# DoXeArduino_RFID.net
KiCad netlist of a schematic drawn in Altium Designer
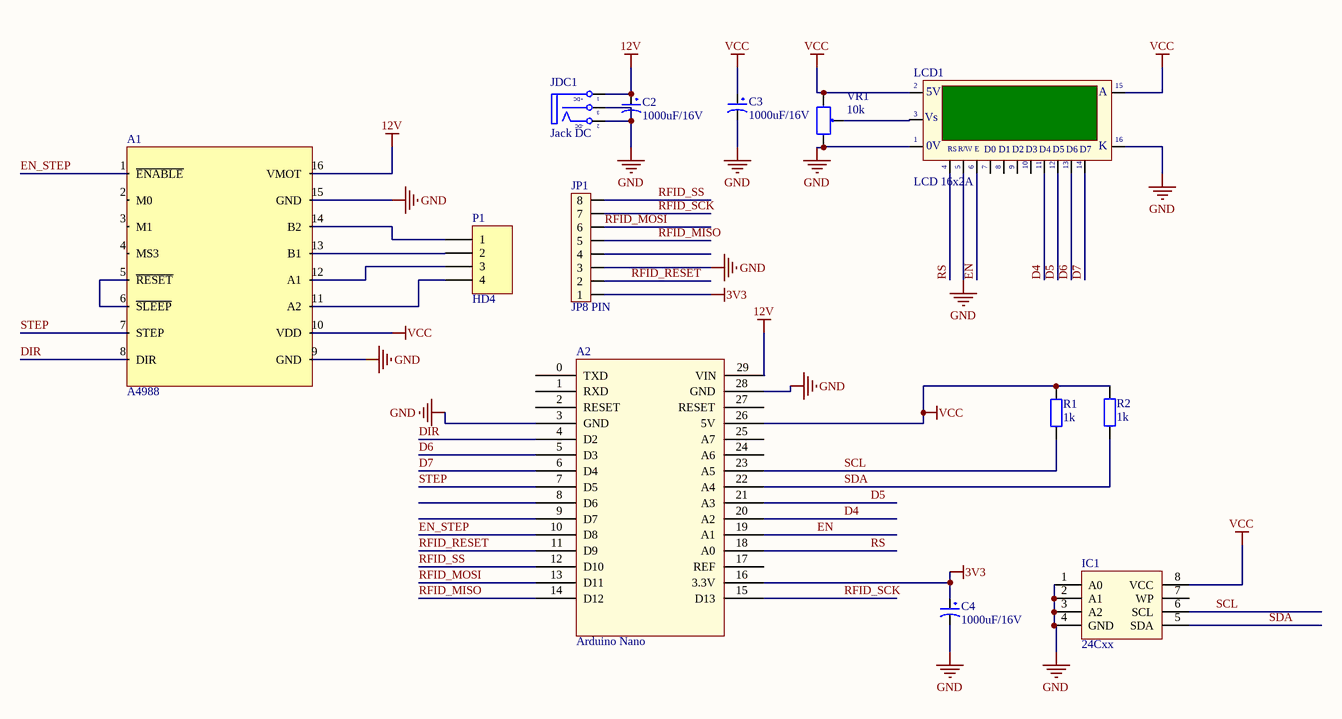
[diagram p0: DoXeArduino_RFID.SchDoc]

(export (version "E")
  (design (tool "Eeschema 10.0.6"))
  (components
    (comp (ref "A1") (value "A4988") (footprint "A4988") (libsource (lib "OBIT_TESLA") (part "A4988")))
    (comp (ref "A2")
      (value "Arduino Nano")
      (footprint "Arduino Nano")
      (libsource (lib "OBIT_TESLA") (part "Arduino Nano"))
    )
    (comp (ref "C2")
      (value "1000uF/16V")
      (footprint "CP1.5/3.4")
      (description "Cap 1000uF/16V - 220uF/50V")
      (libsource (lib "OBIT_TESLA") (part "CP4"))
    )
    (comp (ref "C3")
      (value "1000uF/16V")
      (footprint "CP1.5/3.4")
      (description "Cap 1000uF/16V - 220uF/50V")
      (libsource (lib "OBIT_TESLA") (part "CP4"))
    )
    (comp (ref "C4")
      (value "1000uF/16V")
      (footprint "CP1.5/3.4")
      (description "Cap 1000uF/16V - 220uF/50V")
      (libsource (lib "OBIT_TESLA") (part "CP4"))
    )
    (comp (ref "IC1")
      (value "24Cxx")
      (footprint "DIP8/W0.3")
      (description "Standard 2-Wire Bus Interface Serial EEPROM")
      (fields (field (name "COPYRIGHT BY") "VanDungEvn"))
      (libsource (lib "Obit_Library") (part "24Cxx"))
    )
    (comp (ref "JDC1") (value "Jack DC") (footprint "DC0") (libsource (lib "OBIT_TESLA") (part "JACK_DC")))
    (comp (ref "JP1") (value "JP8 PIN") (footprint "JP8") (libsource (lib "Obit_Library") (part "JP8")))
    (comp (ref "LCD1")
      (value "LCD 16x2A")
      (footprint "LCD16X2")
      (description "LCD dipslay 16 char, 2 line")
      (libsource (lib "OBIT_TESLA") (part "LCD16x2A"))
    )
    (comp (ref "P1") (value "HD4") (footprint "HEADER 4") (libsource (lib "OBIT_TESLA") (part "HEADER 4")))
    (comp (ref "R1")
      (value "1k")
      (footprint "RES-SMD-0805")
      (description "Resistor R1/4W")
      (libsource (lib "OBIT_TESLA") (part "R"))
    )
    (comp (ref "R2")
      (value "1k")
      (footprint "RES-SMD-0805")
      (description "Resistor R1/4W")
      (libsource (lib "OBIT_TESLA") (part "R"))
    )
    (comp (ref "VR1") (value "10k") (footprint "VR-S2") (libsource (lib "OBIT_TESLA") (part "Resistor Var")))
  )
  (nets
    (net (code "1") (name "/D4") (class "Default")
      (node (ref "A2") (pin "20") (pinfunction "A2_20") (pintype "passive"))
      (node (ref "LCD1") (pin "11") (pinfunction "D4_11") (pintype "passive"))
    )
    (net (code "2") (name "/D5") (class "Default")
      (node (ref "A2") (pin "21") (pinfunction "A3_21") (pintype "passive"))
      (node (ref "LCD1") (pin "12") (pinfunction "D5_12") (pintype "passive"))
    )
    (net (code "3") (name "/D6") (class "Default")
      (node (ref "A2") (pin "5") (pinfunction "D3_5") (pintype "passive"))
      (node (ref "LCD1") (pin "13") (pinfunction "D6_13") (pintype "passive"))
    )
    (net (code "4") (name "/D7") (class "Default")
      (node (ref "A2") (pin "6") (pinfunction "D4_6") (pintype "passive"))
      (node (ref "LCD1") (pin "14") (pinfunction "D7_14") (pintype "passive"))
    )
    (net (code "5") (name "/DIR") (class "Default")
      (node (ref "A1") (pin "8") (pinfunction "DIR_8") (pintype "passive"))
      (node (ref "A2") (pin "4") (pinfunction "D2_4") (pintype "passive"))
    )
    (net (code "6") (name "/EN") (class "Default")
      (node (ref "A2") (pin "19") (pinfunction "A1_19") (pintype "passive"))
      (node (ref "LCD1") (pin "6") (pinfunction "~{EN}_6") (pintype "passive"))
    )
    (net (code "7") (name "/EN_STEP") (class "Default")
      (node (ref "A1") (pin "1") (pinfunction "~{ENABLE}_1") (pintype "passive"))
      (node (ref "A2") (pin "10") (pinfunction "D8_10") (pintype "passive"))
    )
    (net (code "8") (name "/RFID_MISO") (class "Default")
      (node (ref "A2") (pin "14") (pinfunction "D12_14") (pintype "passive"))
      (node (ref "JP1") (pin "5") (pinfunction "5_5") (pintype "passive"))
    )
    (net (code "9") (name "/RFID_MOSI") (class "Default")
      (node (ref "A2") (pin "13") (pinfunction "D11_13") (pintype "passive"))
      (node (ref "JP1") (pin "6") (pinfunction "6_6") (pintype "passive"))
    )
    (net (code "10") (name "/RFID_RESET") (class "Default")
      (node (ref "A2") (pin "11") (pinfunction "D9_11") (pintype "passive"))
      (node (ref "JP1") (pin "2") (pinfunction "2_2") (pintype "passive"))
    )
    (net (code "11") (name "/RFID_SCK") (class "Default")
      (node (ref "A2") (pin "15") (pinfunction "D13_15") (pintype "passive"))
      (node (ref "JP1") (pin "7") (pinfunction "7_7") (pintype "passive"))
    )
    (net (code "12") (name "/RFID_SS") (class "Default")
      (node (ref "A2") (pin "12") (pinfunction "D10_12") (pintype "passive"))
      (node (ref "JP1") (pin "8") (pinfunction "8_8") (pintype "passive"))
    )
    (net (code "13") (name "/RS") (class "Default")
      (node (ref "A2") (pin "18") (pinfunction "A0_18") (pintype "passive"))
      (node (ref "LCD1") (pin "4") (pinfunction "RS_4") (pintype "passive"))
    )
    (net (code "14") (name "/SCL") (class "Default")
      (node (ref "A2") (pin "23") (pinfunction "A5_23") (pintype "passive"))
      (node (ref "IC1") (pin "6") (pinfunction "SCL_6") (pintype "passive"))
      (node (ref "R1") (pin "1") (pinfunction "1_1") (pintype "passive"))
    )
    (net (code "15") (name "/SDA") (class "Default")
      (node (ref "A2") (pin "22") (pinfunction "A4_22") (pintype "passive"))
      (node (ref "IC1") (pin "5") (pinfunction "SDA_5") (pintype "passive"))
      (node (ref "R2") (pin "1") (pinfunction "1_1") (pintype "passive"))
    )
    (net (code "16") (name "/STEP") (class "Default")
      (node (ref "A1") (pin "7") (pinfunction "STEP_7") (pintype "passive"))
      (node (ref "A2") (pin "7") (pinfunction "D5_7") (pintype "passive"))
    )
    (net (code "17") (name "3V3") (class "Default")
      (node (ref "A2") (pin "16") (pinfunction "3.3V_16") (pintype "passive"))
      (node (ref "C4") (pin "1") (pinfunction "1_1") (pintype "passive"))
      (node (ref "JP1") (pin "1") (pinfunction "1_1") (pintype "passive"))
    )
    (net (code "18") (name "12V") (class "Default")
      (node (ref "A1") (pin "16") (pinfunction "VMOT_16") (pintype "passive"))
      (node (ref "A2") (pin "29") (pinfunction "VIN_29") (pintype "passive"))
      (node (ref "C2") (pin "1") (pinfunction "1_1") (pintype "passive"))
      (node (ref "JDC1") (pin "1") (pinfunction "T_1") (pintype "passive"))
    )
    (net (code "19") (name "GND") (class "Default")
      (node (ref "A1") (pin "15") (pinfunction "GND_15") (pintype "passive"))
      (node (ref "A1") (pin "9") (pinfunction "GND_9") (pintype "passive"))
      (node (ref "A2") (pin "28") (pinfunction "GND_28") (pintype "passive"))
      (node (ref "A2") (pin "3") (pinfunction "GND_3") (pintype "passive"))
      (node (ref "C2") (pin "2") (pinfunction "2_2") (pintype "passive"))
      (node (ref "C3") (pin "2") (pinfunction "2_2") (pintype "passive"))
      (node (ref "C4") (pin "2") (pinfunction "2_2") (pintype "passive"))
      (node (ref "IC1") (pin "1") (pinfunction "A0_1") (pintype "passive"))
      (node (ref "IC1") (pin "2") (pinfunction "A1_2") (pintype "passive"))
      (node (ref "IC1") (pin "3") (pinfunction "A2_3") (pintype "passive"))
      (node (ref "IC1") (pin "4") (pinfunction "GND_4") (pintype "power_in"))
      (node (ref "JDC1") (pin "2") (pinfunction "TN_2") (pintype "passive"))
      (node (ref "JDC1") (pin "3") (pinfunction "S_3") (pintype "power_in"))
      (node (ref "JP1") (pin "3") (pinfunction "3_3") (pintype "passive"))
      (node (ref "LCD1") (pin "1") (pinfunction "GND_1") (pintype "passive"))
      (node (ref "LCD1") (pin "16") (pinfunction "K_16") (pintype "passive"))
      (node (ref "LCD1") (pin "5") (pinfunction "R/~{W}_5") (pintype "passive"))
      (node (ref "VR1") (pin "3") (pinfunction "3_3") (pintype "passive"))
    )
    (net (code "20") (name "Net-(A1-A1)") (class "Default")
      (node (ref "A1") (pin "12") (pinfunction "A1_12") (pintype "passive"))
      (node (ref "P1") (pin "3") (pinfunction "3_3") (pintype "passive"))
    )
    (net (code "21") (name "Net-(A1-A2)") (class "Default")
      (node (ref "A1") (pin "11") (pinfunction "A2_11") (pintype "passive"))
      (node (ref "P1") (pin "4") (pinfunction "4_4") (pintype "passive"))
    )
    (net (code "22") (name "Net-(A1-B1)") (class "Default")
      (node (ref "A1") (pin "13") (pinfunction "B1_13") (pintype "passive"))
      (node (ref "P1") (pin "2") (pinfunction "2_2") (pintype "passive"))
    )
    (net (code "23") (name "Net-(A1-B2)") (class "Default")
      (node (ref "A1") (pin "14") (pinfunction "B2_14") (pintype "passive"))
      (node (ref "P1") (pin "1") (pinfunction "1_1") (pintype "passive"))
    )
    (net (code "24") (name "Net-(A1-~{RESET})") (class "Default")
      (node (ref "A1") (pin "5") (pinfunction "~{RESET}_5") (pintype "passive"))
      (node (ref "A1") (pin "6") (pinfunction "~{SLEEP}_6") (pintype "passive"))
    )
    (net (code "25") (name "Net-(LCD1-VEE)") (class "Default")
      (node (ref "LCD1") (pin "3") (pinfunction "VEE_3") (pintype "passive"))
      (node (ref "VR1") (pin "2") (pinfunction "2_2") (pintype "passive"))
    )
    (net (code "26") (name "VCC") (class "Default")
      (node (ref "A1") (pin "10") (pinfunction "VDD_10") (pintype "passive"))
      (node (ref "A2") (pin "26") (pinfunction "5V_26") (pintype "passive"))
      (node (ref "C3") (pin "1") (pinfunction "1_1") (pintype "passive"))
      (node (ref "IC1") (pin "8") (pinfunction "VCC_8") (pintype "power_in"))
      (node (ref "LCD1") (pin "15") (pinfunction "A_15") (pintype "passive"))
      (node (ref "LCD1") (pin "2") (pinfunction "VDD_2") (pintype "passive"))
      (node (ref "R1") (pin "2") (pinfunction "2_2") (pintype "passive"))
      (node (ref "R2") (pin "2") (pinfunction "2_2") (pintype "passive"))
      (node (ref "VR1") (pin "1") (pinfunction "1_1") (pintype "passive"))
    )
    (net (code "27") (name "unconnected-(A1-M0-Pad2)") (class "Default")
      (node (ref "A1") (pin "2") (pinfunction "M0_2") (pintype "passive"))
    )
    (net (code "28") (name "unconnected-(A1-M1-Pad3)") (class "Default")
      (node (ref "A1") (pin "3") (pinfunction "M1_3") (pintype "passive"))
    )
    (net (code "29") (name "unconnected-(A1-MS3-Pad4)") (class "Default")
      (node (ref "A1") (pin "4") (pinfunction "MS3_4") (pintype "passive"))
    )
    (net (code "30") (name "unconnected-(A2-A6-Pad24)") (class "Default")
      (node (ref "A2") (pin "24") (pinfunction "A6_24") (pintype "passive"))
    )
    (net (code "31") (name "unconnected-(A2-A7-Pad25)") (class "Default")
      (node (ref "A2") (pin "25") (pinfunction "A7_25") (pintype "passive"))
    )
    (net (code "32") (name "unconnected-(A2-D6-Pad8)") (class "Default")
      (node (ref "A2") (pin "8") (pinfunction "D6_8") (pintype "passive"))
    )
    (net (code "33") (name "unconnected-(A2-D7-Pad9)") (class "Default")
      (node (ref "A2") (pin "9") (pinfunction "D7_9") (pintype "passive"))
    )
    (net (code "34") (name "unconnected-(A2-REF-Pad17)") (class "Default")
      (node (ref "A2") (pin "17") (pinfunction "REF_17") (pintype "passive"))
    )
    (net (code "35") (name "unconnected-(A2-RESET-Pad2)") (class "Default")
      (node (ref "A2") (pin "2") (pinfunction "RESET_2") (pintype "passive"))
    )
    (net (code "36") (name "unconnected-(A2-RESET-Pad27)") (class "Default")
      (node (ref "A2") (pin "27") (pinfunction "RESET_27") (pintype "passive"))
    )
    (net (code "37") (name "unconnected-(A2-RXD-Pad1)") (class "Default")
      (node (ref "A2") (pin "1") (pinfunction "RXD_1") (pintype "passive"))
    )
    (net (code "38") (name "unconnected-(A2-TXD-Pad0)") (class "Default")
      (node (ref "A2") (pin "0") (pinfunction "TXD_0") (pintype "passive"))
    )
    (net (code "39") (name "unconnected-(IC1-WP-Pad7)") (class "Default")
      (node (ref "IC1") (pin "7") (pinfunction "WP_7") (pintype "passive"))
    )
    (net (code "40") (name "unconnected-(JP1-Pad4)") (class "Default")
      (node (ref "JP1") (pin "4") (pinfunction "4_4") (pintype "passive"))
    )
    (net (code "41") (name "unconnected-(LCD1-D0-Pad7)") (class "Default")
      (node (ref "LCD1") (pin "7") (pinfunction "D0_7") (pintype "passive"))
    )
    (net (code "42") (name "unconnected-(LCD1-D1-Pad8)") (class "Default")
      (node (ref "LCD1") (pin "8") (pinfunction "D1_8") (pintype "passive"))
    )
    (net (code "43") (name "unconnected-(LCD1-D2-Pad9)") (class "Default")
      (node (ref "LCD1") (pin "9") (pinfunction "D2_9") (pintype "passive"))
    )
    (net (code "44") (name "unconnected-(LCD1-D3-Pad10)") (class "Default")
      (node (ref "LCD1") (pin "10") (pinfunction "D3_10") (pintype "passive"))
    )
  )
)
